# Metaldetector.net
KiCad netlist of a schematic drawn in EAGLE
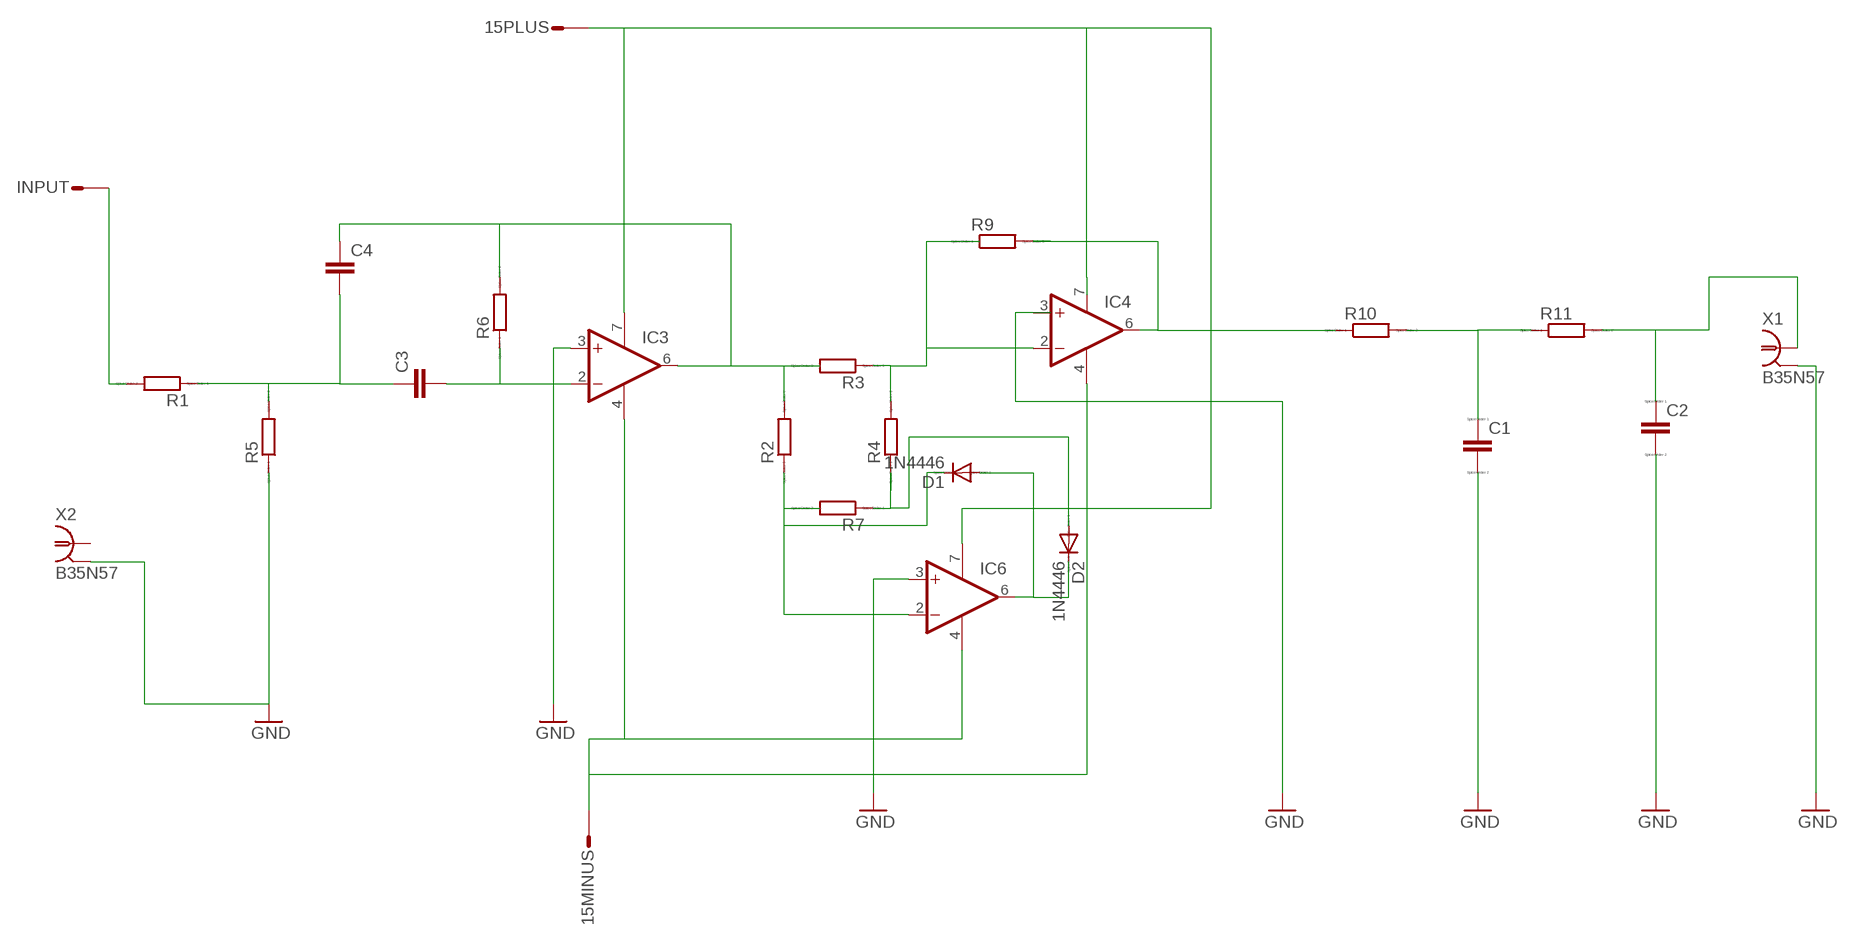
[diagram p0: schematic, sheet 1]

(export (version "E")
  (design (tool "Eeschema 10.0.6"))
  (components
    (comp (ref "15MINUS")
      (value "ST2,8")
      (footprint "eagle-import:ST2,8")
      (libsource (lib "eagle-import") (part "ST2,8"))
    )
    (comp (ref "15PLUS")
      (value "ST2,8")
      (footprint "eagle-import:ST2,8")
      (libsource (lib "eagle-import") (part "ST2,8"))
    )
    (comp (ref "C1")
      (value "C-EU025-040X050")
      (footprint "eagle-import:C025-040X050")
      (libsource (lib "eagle-import") (part "C-EU025-040X050"))
    )
    (comp (ref "C2")
      (value "C-EU025-040X050")
      (footprint "eagle-import:C025-040X050")
      (libsource (lib "eagle-import") (part "C-EU025-040X050"))
    )
    (comp (ref "C3")
      (value "C2.5/5")
      (footprint "eagle-import:C2.5-5")
      (libsource (lib "eagle-import") (part "C2.5/5"))
    )
    (comp (ref "C4")
      (value "C2.5/5")
      (footprint "eagle-import:C2.5-5")
      (libsource (lib "eagle-import") (part "C2.5/5"))
    )
    (comp (ref "D1")
      (value "1N4446")
      (footprint "eagle-import:DO35-10")
      (libsource (lib "eagle-import") (part "1N4446"))
    )
    (comp (ref "D2")
      (value "1N4446")
      (footprint "eagle-import:DO35-10")
      (libsource (lib "eagle-import") (part "1N4446"))
    )
    (comp (ref "IC3")
      (value "1AMP_P7+4N")
      (footprint "eagle-import:DIL08")
      (libsource (lib "eagle-import") (part "1AMP_P7+4N"))
    )
    (comp (ref "IC4")
      (value "1AMP_P7+4N")
      (footprint "eagle-import:DIL08")
      (libsource (lib "eagle-import") (part "1AMP_P7+4N"))
    )
    (comp (ref "IC6")
      (value "1AMP_P7+4N")
      (footprint "eagle-import:DIL08")
      (libsource (lib "eagle-import") (part "1AMP_P7+4N"))
    )
    (comp (ref "INPUT")
      (value "ST2,8")
      (footprint "eagle-import:ST2,8")
      (libsource (lib "eagle-import") (part "ST2,8"))
    )
    (comp (ref "R1")
      (value "R0207/10")
      (footprint "eagle-import:0207_10")
      (libsource (lib "eagle-import") (part "R0207/10"))
    )
    (comp (ref "R2")
      (value "R0207/10")
      (footprint "eagle-import:0207_10")
      (libsource (lib "eagle-import") (part "R0207/10"))
    )
    (comp (ref "R3")
      (value "R0207/10")
      (footprint "eagle-import:0207_10")
      (libsource (lib "eagle-import") (part "R0207/10"))
    )
    (comp (ref "R4")
      (value "R0207/10")
      (footprint "eagle-import:0207_10")
      (libsource (lib "eagle-import") (part "R0207/10"))
    )
    (comp (ref "R5")
      (value "R0207/10")
      (footprint "eagle-import:0207_10")
      (libsource (lib "eagle-import") (part "R0207/10"))
    )
    (comp (ref "R6")
      (value "R0207/10")
      (footprint "eagle-import:0207_10")
      (libsource (lib "eagle-import") (part "R0207/10"))
    )
    (comp (ref "R7")
      (value "R0207/10")
      (footprint "eagle-import:0207_10")
      (libsource (lib "eagle-import") (part "R0207/10"))
    )
    (comp (ref "R9")
      (value "R0207/10")
      (footprint "eagle-import:0207_10")
      (libsource (lib "eagle-import") (part "R0207/10"))
    )
    (comp (ref "R10")
      (value "R0204/7")
      (footprint "eagle-import:0204_7")
      (libsource (lib "eagle-import") (part "R0204/7"))
    )
    (comp (ref "R11")
      (value "R0204/7")
      (footprint "eagle-import:0204_7")
      (libsource (lib "eagle-import") (part "R0204/7"))
    )
    (comp (ref "X1")
      (value "B35N57")
      (footprint "eagle-import:B35N57")
      (libsource (lib "eagle-import") (part "B35N57"))
    )
    (comp (ref "X2")
      (value "B35N57")
      (footprint "eagle-import:B35N57")
      (libsource (lib "eagle-import") (part "B35N57"))
    )
  )
  (nets
    (net (code "1") (name "GND") (class "Default")
      (node (ref "C1") (pin "2") (pinfunction "2_2") (pintype "passive"))
      (node (ref "C2") (pin "2") (pinfunction "2_2") (pintype "passive"))
      (node (ref "IC3") (pin "3") (pinfunction "+IN_3") (pintype "input"))
      (node (ref "IC4") (pin "3") (pinfunction "+IN_3") (pintype "input"))
      (node (ref "IC6") (pin "3") (pinfunction "+IN_3") (pintype "input"))
      (node (ref "R5") (pin "1") (pinfunction "1_1") (pintype "passive"))
      (node (ref "X1") (pin "2") (pinfunction "2_2") (pintype "passive"))
      (node (ref "X1") (pin "3") (pinfunction "2_3") (pintype "passive"))
      (node (ref "X1") (pin "4") (pinfunction "2_4") (pintype "passive"))
      (node (ref "X1") (pin "5") (pinfunction "2_5") (pintype "passive"))
      (node (ref "X2") (pin "2") (pinfunction "2_2") (pintype "passive"))
      (node (ref "X2") (pin "3") (pinfunction "2_3") (pintype "passive"))
      (node (ref "X2") (pin "4") (pinfunction "2_4") (pintype "passive"))
      (node (ref "X2") (pin "5") (pinfunction "2_5") (pintype "passive"))
    )
    (net (code "2") (name "Net-(15MINUS-ST)") (class "Default")
      (node (ref "15MINUS") (pin "1") (pinfunction "ST_1") (pintype "passive"))
      (node (ref "IC3") (pin "4") (pinfunction "V-_4") (pintype "power_in"))
      (node (ref "IC4") (pin "4") (pinfunction "V-_4") (pintype "power_in"))
      (node (ref "IC6") (pin "4") (pinfunction "V-_4") (pintype "power_in"))
    )
    (net (code "3") (name "Net-(15PLUS-ST)") (class "Default")
      (node (ref "15PLUS") (pin "1") (pinfunction "ST_1") (pintype "passive"))
      (node (ref "IC3") (pin "7") (pinfunction "V+_7") (pintype "power_in"))
      (node (ref "IC4") (pin "7") (pinfunction "V+_7") (pintype "power_in"))
      (node (ref "IC6") (pin "7") (pinfunction "V+_7") (pintype "power_in"))
    )
    (net (code "4") (name "Net-(C1-Pad1)") (class "Default")
      (node (ref "C1") (pin "1") (pinfunction "1_1") (pintype "passive"))
      (node (ref "R10") (pin "2") (pinfunction "2_2") (pintype "passive"))
      (node (ref "R11") (pin "1") (pinfunction "1_1") (pintype "passive"))
    )
    (net (code "5") (name "Net-(C2-Pad1)") (class "Default")
      (node (ref "C2") (pin "1") (pinfunction "1_1") (pintype "passive"))
      (node (ref "R11") (pin "2") (pinfunction "2_2") (pintype "passive"))
      (node (ref "X1") (pin "1") (pinfunction "1_1") (pintype "passive"))
    )
    (net (code "6") (name "Net-(C3-Pad1)") (class "Default")
      (node (ref "C3") (pin "1") (pinfunction "1_1") (pintype "passive"))
      (node (ref "C4") (pin "2") (pinfunction "2_2") (pintype "passive"))
      (node (ref "R1") (pin "1") (pinfunction "1_1") (pintype "passive"))
      (node (ref "R5") (pin "2") (pinfunction "2_2") (pintype "passive"))
    )
    (net (code "7") (name "Net-(D2-PadA)") (class "Default")
      (node (ref "D2") (pin "A") (pinfunction "A_A") (pintype "passive"))
      (node (ref "R4") (pin "1") (pinfunction "1_1") (pintype "passive"))
      (node (ref "R7") (pin "1") (pinfunction "1_1") (pintype "passive"))
    )
    (net (code "8") (name "Net-(IC3--IN)") (class "Default")
      (node (ref "C3") (pin "2") (pinfunction "2_2") (pintype "passive"))
      (node (ref "IC3") (pin "2") (pinfunction "-IN_2") (pintype "input"))
      (node (ref "R6") (pin "1") (pinfunction "1_1") (pintype "passive"))
    )
    (net (code "9") (name "Net-(IC3-OUT)") (class "Default")
      (node (ref "C4") (pin "1") (pinfunction "1_1") (pintype "passive"))
      (node (ref "IC3") (pin "6") (pinfunction "OUT_6") (pintype "output"))
      (node (ref "R2") (pin "2") (pinfunction "2_2") (pintype "passive"))
      (node (ref "R3") (pin "2") (pinfunction "2_2") (pintype "passive"))
      (node (ref "R6") (pin "2") (pinfunction "2_2") (pintype "passive"))
    )
    (net (code "10") (name "Net-(IC4--IN)") (class "Default")
      (node (ref "IC4") (pin "2") (pinfunction "-IN_2") (pintype "input"))
      (node (ref "R3") (pin "1") (pinfunction "1_1") (pintype "passive"))
      (node (ref "R4") (pin "2") (pinfunction "2_2") (pintype "passive"))
      (node (ref "R9") (pin "1") (pinfunction "1_1") (pintype "passive"))
    )
    (net (code "11") (name "Net-(IC4-OUT)") (class "Default")
      (node (ref "IC4") (pin "6") (pinfunction "OUT_6") (pintype "output"))
      (node (ref "R10") (pin "1") (pinfunction "1_1") (pintype "passive"))
      (node (ref "R9") (pin "2") (pinfunction "2_2") (pintype "passive"))
    )
    (net (code "12") (name "Net-(IC6--IN)") (class "Default")
      (node (ref "D1") (pin "C") (pinfunction "C_C") (pintype "passive"))
      (node (ref "IC6") (pin "2") (pinfunction "-IN_2") (pintype "input"))
      (node (ref "R2") (pin "1") (pinfunction "1_1") (pintype "passive"))
      (node (ref "R7") (pin "2") (pinfunction "2_2") (pintype "passive"))
    )
    (net (code "13") (name "Net-(IC6-OUT)") (class "Default")
      (node (ref "D1") (pin "A") (pinfunction "A_A") (pintype "passive"))
      (node (ref "D2") (pin "C") (pinfunction "C_C") (pintype "passive"))
      (node (ref "IC6") (pin "6") (pinfunction "OUT_6") (pintype "output"))
    )
    (net (code "14") (name "Net-(INPUT-ST)") (class "Default")
      (node (ref "INPUT") (pin "1") (pinfunction "ST_1") (pintype "passive"))
      (node (ref "R1") (pin "2") (pinfunction "2_2") (pintype "passive"))
    )
    (net (code "15") (name "unconnected-(X2-Pad1)") (class "Default")
      (node (ref "X2") (pin "1") (pinfunction "1_1") (pintype "passive"))
    )
  )
)
